# obd25k80.net
KiCad netlist of a schematic drawn in EAGLE
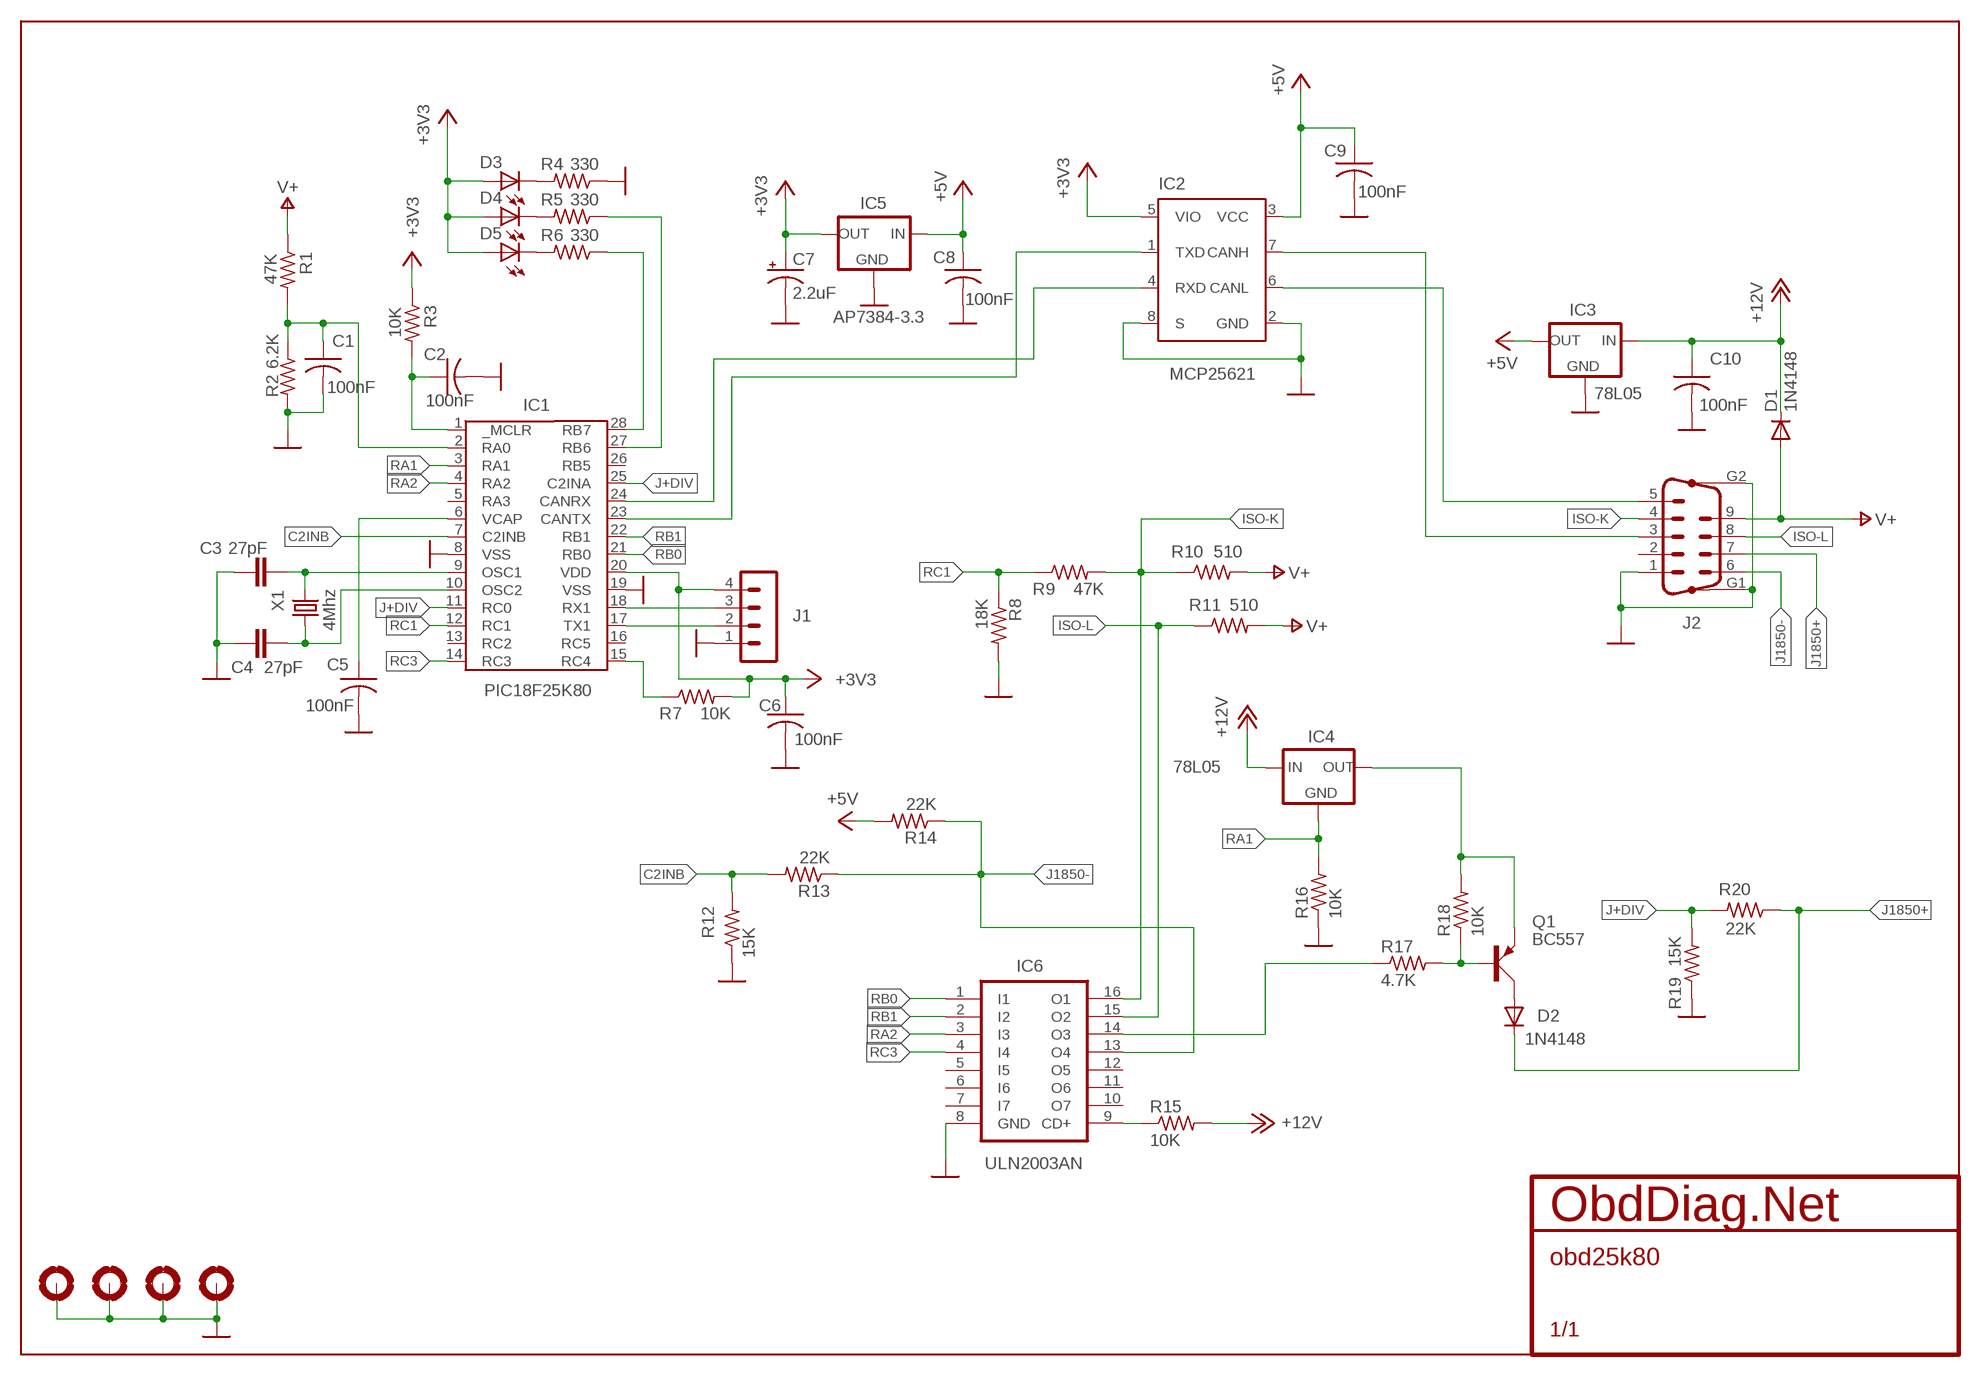
[diagram p0: schematic, sheet 1]

(export (version "E")
  (design (tool "Eeschema 10.0.6"))
  (components
    (comp (ref "C1")
      (value "100nF")
      (footprint "eagle-import:C050-025X075")
      (libsource (lib "eagle-import") (part "C-US050-025X075"))
    )
    (comp (ref "C2")
      (value "100nF")
      (footprint "eagle-import:C050-025X075")
      (libsource (lib "eagle-import") (part "C-US050-025X075"))
    )
    (comp (ref "C3")
      (value "27pF")
      (footprint "eagle-import:C2.5-2")
      (libsource (lib "eagle-import") (part "C2.5/2"))
    )
    (comp (ref "C4")
      (value "27pF")
      (footprint "eagle-import:C2.5-2")
      (libsource (lib "eagle-import") (part "C2.5/2"))
    )
    (comp (ref "C5")
      (value "100nF")
      (footprint "eagle-import:C050-025X075")
      (libsource (lib "eagle-import") (part "C-US050-025X075"))
    )
    (comp (ref "C6")
      (value "100nF")
      (footprint "eagle-import:C050-025X075")
      (libsource (lib "eagle-import") (part "C-US050-025X075"))
    )
    (comp (ref "C7")
      (value "2.2uF")
      (footprint "eagle-import:E2,5-5")
      (libsource (lib "eagle-import") (part "CPOL-USE2.5-5"))
    )
    (comp (ref "C8")
      (value "100nF")
      (footprint "eagle-import:C050-025X075")
      (libsource (lib "eagle-import") (part "C-US050-025X075"))
    )
    (comp (ref "C9")
      (value "100nF")
      (footprint "eagle-import:C050-025X075")
      (libsource (lib "eagle-import") (part "C-US050-025X075"))
    )
    (comp (ref "C10")
      (value "100nF")
      (footprint "eagle-import:C050-025X075")
      (libsource (lib "eagle-import") (part "C-US050-025X075"))
    )
    (comp (ref "D1")
      (value "1N4148")
      (footprint "eagle-import:D035-10M")
      (libsource (lib "eagle-import") (part "1N4148M"))
    )
    (comp (ref "D2")
      (value "1N4148")
      (footprint "eagle-import:D035-10M")
      (libsource (lib "eagle-import") (part "1N4148M"))
    )
    (comp (ref "D3")
      (value "LED5MM")
      (footprint "eagle-import:LED5MM")
      (libsource (lib "eagle-import") (part "LED5MM"))
    )
    (comp (ref "D4")
      (value "LED5MM")
      (footprint "eagle-import:LED5MM")
      (libsource (lib "eagle-import") (part "LED5MM"))
    )
    (comp (ref "D5")
      (value "LED5MM")
      (footprint "eagle-import:LED5MM")
      (libsource (lib "eagle-import") (part "LED5MM"))
    )
    (comp (ref "H1")
      (value "MOUNT-PAD-ROUND2.8")
      (footprint "eagle-import:2,8-PAD")
      (libsource (lib "eagle-import") (part "MOUNT-PAD-ROUND2.8"))
    )
    (comp (ref "H2")
      (value "MOUNT-PAD-ROUND2.8")
      (footprint "eagle-import:2,8-PAD")
      (libsource (lib "eagle-import") (part "MOUNT-PAD-ROUND2.8"))
    )
    (comp (ref "H3")
      (value "MOUNT-PAD-ROUND2.8")
      (footprint "eagle-import:2,8-PAD")
      (libsource (lib "eagle-import") (part "MOUNT-PAD-ROUND2.8"))
    )
    (comp (ref "H4")
      (value "MOUNT-PAD-ROUND2.8")
      (footprint "eagle-import:2,8-PAD")
      (libsource (lib "eagle-import") (part "MOUNT-PAD-ROUND2.8"))
    )
    (comp (ref "IC1")
      (value "PIC18F25K80")
      (footprint "eagle-import:DIL28")
      (libsource (lib "eagle-import") (part "PIC18F25K80-2"))
    )
    (comp (ref "IC2")
      (value "MCP25621")
      (footprint "eagle-import:DIL8")
      (libsource (lib "eagle-import") (part "MCP25621"))
    )
    (comp (ref "IC3")
      (value "78L05")
      (footprint "eagle-import:78LXX")
      (libsource (lib "eagle-import") (part "78LXX"))
    )
    (comp (ref "IC4")
      (value "78L05")
      (footprint "eagle-import:78LXX")
      (libsource (lib "eagle-import") (part "78LXX"))
    )
    (comp (ref "IC5")
      (value "AP7384-3.3")
      (footprint "eagle-import:TO92")
      (libsource (lib "eagle-import") (part "AP7384"))
    )
    (comp (ref "IC6")
      (value "ULN2003AN")
      (footprint "eagle-import:DIL16")
      (libsource (lib "eagle-import") (part "ULN2003AN"))
    )
    (comp (ref "J1")
      (value "MA04-1")
      (footprint "eagle-import:MA04-1")
      (libsource (lib "eagle-import") (part "MA04-1"))
    )
    (comp (ref "J2")
      (value "DB9-M")
      (footprint "eagle-import:M09HP")
      (libsource (lib "eagle-import") (part "M09HP"))
    )
    (comp (ref "Q1")
      (value "BC557")
      (footprint "eagle-import:SOT54A")
      (libsource (lib "eagle-import") (part "BC557"))
    )
    (comp (ref "R1")
      (value "47K")
      (footprint "eagle-import:0207_10")
      (libsource (lib "eagle-import") (part "R-US_0207/10"))
    )
    (comp (ref "R2")
      (value "6.2K")
      (footprint "eagle-import:0207_10")
      (libsource (lib "eagle-import") (part "R-US_0207/10"))
    )
    (comp (ref "R3")
      (value "10K")
      (footprint "eagle-import:0207_10")
      (libsource (lib "eagle-import") (part "R-US_0207/10"))
    )
    (comp (ref "R4")
      (value "330")
      (footprint "eagle-import:0207_10")
      (libsource (lib "eagle-import") (part "R-US_0207/10"))
    )
    (comp (ref "R5")
      (value "330")
      (footprint "eagle-import:0207_10")
      (libsource (lib "eagle-import") (part "R-US_0207/10"))
    )
    (comp (ref "R6")
      (value "330")
      (footprint "eagle-import:0207_10")
      (libsource (lib "eagle-import") (part "R-US_0207/10"))
    )
    (comp (ref "R7")
      (value "10K")
      (footprint "eagle-import:0207_10")
      (libsource (lib "eagle-import") (part "R-US_0207/10"))
    )
    (comp (ref "R8")
      (value "18K")
      (footprint "eagle-import:0207_10")
      (libsource (lib "eagle-import") (part "R-US_0207/10"))
    )
    (comp (ref "R9")
      (value "47K")
      (footprint "eagle-import:0207_10")
      (libsource (lib "eagle-import") (part "R-US_0207/10"))
    )
    (comp (ref "R10")
      (value "510")
      (footprint "eagle-import:0207_10")
      (libsource (lib "eagle-import") (part "R-US_0207/10"))
    )
    (comp (ref "R11")
      (value "510")
      (footprint "eagle-import:0207_10")
      (libsource (lib "eagle-import") (part "R-US_0207/10"))
    )
    (comp (ref "R12")
      (value "15K")
      (footprint "eagle-import:0207_10")
      (libsource (lib "eagle-import") (part "R-US_0207/10"))
    )
    (comp (ref "R13")
      (value "22K")
      (footprint "eagle-import:0207_10")
      (libsource (lib "eagle-import") (part "R-US_0207/10"))
    )
    (comp (ref "R14")
      (value "22K")
      (footprint "eagle-import:0207_10")
      (libsource (lib "eagle-import") (part "R-US_0207/10"))
    )
    (comp (ref "R15")
      (value "10K")
      (footprint "eagle-import:0207_10")
      (libsource (lib "eagle-import") (part "R-US_0207/10"))
    )
    (comp (ref "R16")
      (value "10K")
      (footprint "eagle-import:0207_10")
      (libsource (lib "eagle-import") (part "R-US_0207/10"))
    )
    (comp (ref "R17")
      (value "4.7K")
      (footprint "eagle-import:0207_10")
      (libsource (lib "eagle-import") (part "R-US_0207/10"))
    )
    (comp (ref "R18")
      (value "10K")
      (footprint "eagle-import:0207_10")
      (libsource (lib "eagle-import") (part "R-US_0207/10"))
    )
    (comp (ref "R19")
      (value "15K")
      (footprint "eagle-import:0207_10")
      (libsource (lib "eagle-import") (part "R-US_0207/10"))
    )
    (comp (ref "R20")
      (value "22K")
      (footprint "eagle-import:0207_10")
      (libsource (lib "eagle-import") (part "R-US_0207/10"))
    )
    (comp (ref "X1")
      (value "4Mhz")
      (footprint "eagle-import:HC49_S")
      (libsource (lib "eagle-import") (part "CRYTALHC49S"))
    )
  )
  (nets
    (net (code "1") (name "+3V3") (class "Default")
      (node (ref "C6") (pin "1") (pinfunction "1_1") (pintype "passive"))
      (node (ref "C7") (pin "+") (pinfunction "+_+") (pintype "passive"))
      (node (ref "D3") (pin "A") (pinfunction "A_A") (pintype "passive"))
      (node (ref "D4") (pin "A") (pinfunction "A_A") (pintype "passive"))
      (node (ref "D5") (pin "A") (pinfunction "A_A") (pintype "passive"))
      (node (ref "IC1") (pin "20") (pinfunction "VDD_20") (pintype "power_in"))
      (node (ref "IC2") (pin "5") (pinfunction "VIO_5") (pintype "power_in"))
      (node (ref "IC5") (pin "3") (pinfunction "OUT_3") (pintype "passive"))
      (node (ref "J1") (pin "4") (pinfunction "4_4") (pintype "passive"))
      (node (ref "R3") (pin "1") (pinfunction "1_1") (pintype "passive"))
      (node (ref "R7") (pin "2") (pinfunction "2_2") (pintype "passive"))
    )
    (net (code "2") (name "+5V") (class "Default")
      (node (ref "C8") (pin "1") (pinfunction "1_1") (pintype "passive"))
      (node (ref "C9") (pin "1") (pinfunction "1_1") (pintype "passive"))
      (node (ref "IC2") (pin "3") (pinfunction "VCC_3") (pintype "power_in"))
      (node (ref "IC3") (pin "OUT") (pinfunction "OUT_OUT") (pintype "passive"))
      (node (ref "IC5") (pin "1") (pinfunction "IN_1") (pintype "input"))
      (node (ref "R14") (pin "2") (pinfunction "2_2") (pintype "passive"))
    )
    (net (code "3") (name "+12V") (class "Default")
      (node (ref "C10") (pin "1") (pinfunction "1_1") (pintype "passive"))
      (node (ref "D1") (pin "C") (pinfunction "C_C") (pintype "passive"))
      (node (ref "IC3") (pin "IN") (pinfunction "IN_IN") (pintype "input"))
      (node (ref "IC4") (pin "IN") (pinfunction "IN_IN") (pintype "input"))
      (node (ref "R15") (pin "2") (pinfunction "2_2") (pintype "passive"))
    )
    (net (code "4") (name "C2INB") (class "Default")
      (node (ref "IC1") (pin "7") (pinfunction "C2INB_7") (pintype "input"))
      (node (ref "R12") (pin "2") (pinfunction "2_2") (pintype "passive"))
      (node (ref "R13") (pin "2") (pinfunction "2_2") (pintype "passive"))
    )
    (net (code "5") (name "GND") (class "Default")
      (node (ref "C1") (pin "2") (pinfunction "2_2") (pintype "passive"))
      (node (ref "C10") (pin "2") (pinfunction "2_2") (pintype "passive"))
      (node (ref "C2") (pin "2") (pinfunction "2_2") (pintype "passive"))
      (node (ref "C3") (pin "1") (pinfunction "1_1") (pintype "passive"))
      (node (ref "C4") (pin "2") (pinfunction "2_2") (pintype "passive"))
      (node (ref "C5") (pin "2") (pinfunction "2_2") (pintype "passive"))
      (node (ref "C6") (pin "2") (pinfunction "2_2") (pintype "passive"))
      (node (ref "C7") (pin "-") (pinfunction "-_-") (pintype "passive"))
      (node (ref "C8") (pin "2") (pinfunction "2_2") (pintype "passive"))
      (node (ref "C9") (pin "2") (pinfunction "2_2") (pintype "passive"))
      (node (ref "H1") (pin "B2,8") (pinfunction "MOUNT_B2,8") (pintype "passive"))
      (node (ref "H2") (pin "B2,8") (pinfunction "MOUNT_B2,8") (pintype "passive"))
      (node (ref "H3") (pin "B2,8") (pinfunction "MOUNT_B2,8") (pintype "passive"))
      (node (ref "H4") (pin "B2,8") (pinfunction "MOUNT_B2,8") (pintype "passive"))
      (node (ref "IC1") (pin "19") (pinfunction "VSS_19") (pintype "power_in"))
      (node (ref "IC1") (pin "8") (pinfunction "VSS_8") (pintype "power_in"))
      (node (ref "IC2") (pin "2") (pinfunction "GND_2") (pintype "power_in"))
      (node (ref "IC2") (pin "8") (pinfunction "S_8") (pintype "input"))
      (node (ref "IC3") (pin "GND") (pinfunction "GND_GND") (pintype "input"))
      (node (ref "IC5") (pin "2") (pinfunction "GND_2") (pintype "input"))
      (node (ref "IC6") (pin "8") (pinfunction "GND_8") (pintype "power_in"))
      (node (ref "J1") (pin "1") (pinfunction "1_1") (pintype "passive"))
      (node (ref "J2") (pin "1") (pinfunction "1_1") (pintype "passive"))
      (node (ref "J2") (pin "G1") (pinfunction "G1_G1") (pintype "passive"))
      (node (ref "J2") (pin "G2") (pinfunction "G2_G2") (pintype "passive"))
      (node (ref "R12") (pin "1") (pinfunction "1_1") (pintype "passive"))
      (node (ref "R16") (pin "1") (pinfunction "1_1") (pintype "passive"))
      (node (ref "R19") (pin "1") (pinfunction "1_1") (pintype "passive"))
      (node (ref "R2") (pin "2") (pinfunction "2_2") (pintype "passive"))
      (node (ref "R4") (pin "1") (pinfunction "1_1") (pintype "passive"))
      (node (ref "R8") (pin "2") (pinfunction "2_2") (pintype "passive"))
    )
    (net (code "6") (name "ISO-K") (class "Default")
      (node (ref "IC6") (pin "16") (pinfunction "O1_16") (pintype "open_collector"))
      (node (ref "J2") (pin "4") (pinfunction "4_4") (pintype "passive"))
      (node (ref "R10") (pin "1") (pinfunction "1_1") (pintype "passive"))
      (node (ref "R9") (pin "2") (pinfunction "2_2") (pintype "passive"))
    )
    (net (code "7") (name "ISO-L") (class "Default")
      (node (ref "IC6") (pin "15") (pinfunction "O2_15") (pintype "open_collector"))
      (node (ref "J2") (pin "8") (pinfunction "8_8") (pintype "passive"))
      (node (ref "R11") (pin "1") (pinfunction "1_1") (pintype "passive"))
    )
    (net (code "8") (name "J+DIV") (class "Default")
      (node (ref "IC1") (pin "11") (pinfunction "RC0_11") (pintype "bidirectional"))
      (node (ref "IC1") (pin "25") (pinfunction "C2INA_25") (pintype "input"))
      (node (ref "R19") (pin "2") (pinfunction "2_2") (pintype "passive"))
      (node (ref "R20") (pin "2") (pinfunction "2_2") (pintype "passive"))
    )
    (net (code "9") (name "J1850+") (class "Default")
      (node (ref "D2") (pin "C") (pinfunction "C_C") (pintype "passive"))
      (node (ref "J2") (pin "7") (pinfunction "7_7") (pintype "passive"))
      (node (ref "R20") (pin "1") (pinfunction "1_1") (pintype "passive"))
    )
    (net (code "10") (name "J1850-") (class "Default")
      (node (ref "IC6") (pin "13") (pinfunction "O4_13") (pintype "open_collector"))
      (node (ref "J2") (pin "6") (pinfunction "6_6") (pintype "passive"))
      (node (ref "R13") (pin "1") (pinfunction "1_1") (pintype "passive"))
      (node (ref "R14") (pin "1") (pinfunction "1_1") (pintype "passive"))
    )
    (net (code "11") (name "Net-(D2-PadA)") (class "Default")
      (node (ref "D2") (pin "A") (pinfunction "A_A") (pintype "passive"))
      (node (ref "Q1") (pin "C") (pinfunction "C_C") (pintype "passive"))
    )
    (net (code "12") (name "Net-(D3-C)") (class "Default")
      (node (ref "D3") (pin "K") (pinfunction "C_K") (pintype "passive"))
      (node (ref "R4") (pin "2") (pinfunction "2_2") (pintype "passive"))
    )
    (net (code "13") (name "Net-(D4-C)") (class "Default")
      (node (ref "D4") (pin "K") (pinfunction "C_K") (pintype "passive"))
      (node (ref "R5") (pin "2") (pinfunction "2_2") (pintype "passive"))
    )
    (net (code "14") (name "Net-(D5-C)") (class "Default")
      (node (ref "D5") (pin "K") (pinfunction "C_K") (pintype "passive"))
      (node (ref "R6") (pin "2") (pinfunction "2_2") (pintype "passive"))
    )
    (net (code "15") (name "Net-(IC1-CANRX)") (class "Default")
      (node (ref "IC1") (pin "24") (pinfunction "CANRX_24") (pintype "bidirectional"))
      (node (ref "IC2") (pin "4") (pinfunction "RXD_4") (pintype "output"))
    )
    (net (code "16") (name "Net-(IC1-CANTX)") (class "Default")
      (node (ref "IC1") (pin "23") (pinfunction "CANTX_23") (pintype "bidirectional"))
      (node (ref "IC2") (pin "1") (pinfunction "TXD_1") (pintype "input"))
    )
    (net (code "17") (name "Net-(IC1-OSC1)") (class "Default")
      (node (ref "C3") (pin "2") (pinfunction "2_2") (pintype "passive"))
      (node (ref "IC1") (pin "9") (pinfunction "OSC1_9") (pintype "bidirectional"))
      (node (ref "X1") (pin "2") (pinfunction "2_2") (pintype "passive"))
    )
    (net (code "18") (name "Net-(IC1-OSC2)") (class "Default")
      (node (ref "C4") (pin "1") (pinfunction "1_1") (pintype "passive"))
      (node (ref "IC1") (pin "10") (pinfunction "OSC2_10") (pintype "bidirectional"))
      (node (ref "X1") (pin "1") (pinfunction "1_1") (pintype "passive"))
    )
    (net (code "19") (name "Net-(IC1-RA0)") (class "Default")
      (node (ref "C1") (pin "1") (pinfunction "1_1") (pintype "passive"))
      (node (ref "IC1") (pin "2") (pinfunction "RA0_2") (pintype "bidirectional"))
      (node (ref "R1") (pin "2") (pinfunction "2_2") (pintype "passive"))
      (node (ref "R2") (pin "1") (pinfunction "1_1") (pintype "passive"))
    )
    (net (code "20") (name "Net-(IC1-RB6)") (class "Default")
      (node (ref "IC1") (pin "27") (pinfunction "RB6_27") (pintype "bidirectional"))
      (node (ref "R5") (pin "1") (pinfunction "1_1") (pintype "passive"))
    )
    (net (code "21") (name "Net-(IC1-RB7)") (class "Default")
      (node (ref "IC1") (pin "28") (pinfunction "RB7_28") (pintype "bidirectional"))
      (node (ref "R6") (pin "1") (pinfunction "1_1") (pintype "passive"))
    )
    (net (code "22") (name "Net-(IC1-RC4)") (class "Default")
      (node (ref "IC1") (pin "15") (pinfunction "RC4_15") (pintype "bidirectional"))
      (node (ref "R7") (pin "1") (pinfunction "1_1") (pintype "passive"))
    )
    (net (code "23") (name "Net-(IC1-RX1)") (class "Default")
      (node (ref "IC1") (pin "18") (pinfunction "RX1_18") (pintype "bidirectional"))
      (node (ref "J1") (pin "3") (pinfunction "3_3") (pintype "passive"))
    )
    (net (code "24") (name "Net-(IC1-TX1)") (class "Default")
      (node (ref "IC1") (pin "17") (pinfunction "TX1_17") (pintype "bidirectional"))
      (node (ref "J1") (pin "2") (pinfunction "2_2") (pintype "passive"))
    )
    (net (code "25") (name "Net-(IC1-VCAP)") (class "Default")
      (node (ref "C5") (pin "1") (pinfunction "1_1") (pintype "passive"))
      (node (ref "IC1") (pin "6") (pinfunction "VCAP_6") (pintype "passive"))
    )
    (net (code "26") (name "Net-(IC1-_MCLR)") (class "Default")
      (node (ref "C2") (pin "1") (pinfunction "1_1") (pintype "passive"))
      (node (ref "IC1") (pin "1") (pinfunction "_MCLR_1") (pintype "bidirectional"))
      (node (ref "R3") (pin "2") (pinfunction "2_2") (pintype "passive"))
    )
    (net (code "27") (name "Net-(IC2-CANH)") (class "Default")
      (node (ref "IC2") (pin "7") (pinfunction "CANH_7") (pintype "bidirectional"))
      (node (ref "J2") (pin "3") (pinfunction "3_3") (pintype "passive"))
    )
    (net (code "28") (name "Net-(IC2-CANL)") (class "Default")
      (node (ref "IC2") (pin "6") (pinfunction "CANL_6") (pintype "bidirectional"))
      (node (ref "J2") (pin "5") (pinfunction "5_5") (pintype "passive"))
    )
    (net (code "29") (name "Net-(IC4-PadOUT)") (class "Default")
      (node (ref "IC4") (pin "OUT") (pinfunction "OUT_OUT") (pintype "passive"))
      (node (ref "Q1") (pin "E") (pinfunction "E_E") (pintype "passive"))
      (node (ref "R18") (pin "2") (pinfunction "2_2") (pintype "passive"))
    )
    (net (code "30") (name "Net-(IC6-CD+)") (class "Default")
      (node (ref "IC6") (pin "9") (pinfunction "CD+_9") (pintype "passive"))
      (node (ref "R15") (pin "1") (pinfunction "1_1") (pintype "passive"))
    )
    (net (code "31") (name "Net-(IC6-O3)") (class "Default")
      (node (ref "IC6") (pin "14") (pinfunction "O3_14") (pintype "open_collector"))
      (node (ref "R17") (pin "1") (pinfunction "1_1") (pintype "passive"))
    )
    (net (code "32") (name "Net-(Q1-PadB)") (class "Default")
      (node (ref "Q1") (pin "B") (pinfunction "B_B") (pintype "passive"))
      (node (ref "R17") (pin "2") (pinfunction "2_2") (pintype "passive"))
      (node (ref "R18") (pin "1") (pinfunction "1_1") (pintype "passive"))
    )
    (net (code "33") (name "RA1") (class "Default")
      (node (ref "IC1") (pin "3") (pinfunction "RA1_3") (pintype "bidirectional"))
      (node (ref "IC4") (pin "GND") (pinfunction "GND_GND") (pintype "input"))
      (node (ref "R16") (pin "2") (pinfunction "2_2") (pintype "passive"))
    )
    (net (code "34") (name "RA2") (class "Default")
      (node (ref "IC1") (pin "4") (pinfunction "RA2_4") (pintype "bidirectional"))
      (node (ref "IC6") (pin "3") (pinfunction "I3_3") (pintype "input"))
    )
    (net (code "35") (name "RB0") (class "Default")
      (node (ref "IC1") (pin "21") (pinfunction "RB0_21") (pintype "bidirectional"))
      (node (ref "IC6") (pin "1") (pinfunction "I1_1") (pintype "input"))
    )
    (net (code "36") (name "RB1") (class "Default")
      (node (ref "IC1") (pin "22") (pinfunction "RB1_22") (pintype "bidirectional"))
      (node (ref "IC6") (pin "2") (pinfunction "I2_2") (pintype "input"))
    )
    (net (code "37") (name "RC1") (class "Default")
      (node (ref "IC1") (pin "12") (pinfunction "RC1_12") (pintype "bidirectional"))
      (node (ref "R8") (pin "1") (pinfunction "1_1") (pintype "passive"))
      (node (ref "R9") (pin "1") (pinfunction "1_1") (pintype "passive"))
    )
    (net (code "38") (name "RC3") (class "Default")
      (node (ref "IC1") (pin "14") (pinfunction "RC3_14") (pintype "bidirectional"))
      (node (ref "IC6") (pin "4") (pinfunction "I4_4") (pintype "input"))
    )
    (net (code "39") (name "V+") (class "Default")
      (node (ref "D1") (pin "A") (pinfunction "A_A") (pintype "passive"))
      (node (ref "J2") (pin "9") (pinfunction "9_9") (pintype "passive"))
      (node (ref "R1") (pin "1") (pinfunction "1_1") (pintype "passive"))
      (node (ref "R10") (pin "2") (pinfunction "2_2") (pintype "passive"))
      (node (ref "R11") (pin "2") (pinfunction "2_2") (pintype "passive"))
    )
    (net (code "40") (name "unconnected-(IC1-RA3-Pad5)") (class "Default")
      (node (ref "IC1") (pin "5") (pinfunction "RA3_5") (pintype "bidirectional"))
    )
    (net (code "41") (name "unconnected-(IC1-RB5-Pad26)") (class "Default")
      (node (ref "IC1") (pin "26") (pinfunction "RB5_26") (pintype "bidirectional"))
    )
    (net (code "42") (name "unconnected-(IC1-RC2-Pad13)") (class "Default")
      (node (ref "IC1") (pin "13") (pinfunction "RC2_13") (pintype "bidirectional"))
    )
    (net (code "43") (name "unconnected-(IC1-RC5-Pad16)") (class "Default")
      (node (ref "IC1") (pin "16") (pinfunction "RC5_16") (pintype "bidirectional"))
    )
    (net (code "44") (name "unconnected-(IC6-I5-Pad5)") (class "Default")
      (node (ref "IC6") (pin "5") (pinfunction "I5_5") (pintype "input"))
    )
    (net (code "45") (name "unconnected-(IC6-I6-Pad6)") (class "Default")
      (node (ref "IC6") (pin "6") (pinfunction "I6_6") (pintype "input"))
    )
    (net (code "46") (name "unconnected-(IC6-I7-Pad7)") (class "Default")
      (node (ref "IC6") (pin "7") (pinfunction "I7_7") (pintype "input"))
    )
    (net (code "47") (name "unconnected-(IC6-O5-Pad12)") (class "Default")
      (node (ref "IC6") (pin "12") (pinfunction "O5_12") (pintype "open_collector"))
    )
    (net (code "48") (name "unconnected-(IC6-O6-Pad11)") (class "Default")
      (node (ref "IC6") (pin "11") (pinfunction "O6_11") (pintype "open_collector"))
    )
    (net (code "49") (name "unconnected-(IC6-O7-Pad10)") (class "Default")
      (node (ref "IC6") (pin "10") (pinfunction "O7_10") (pintype "open_collector"))
    )
    (net (code "50") (name "unconnected-(J2-Pad2)") (class "Default")
      (node (ref "J2") (pin "2") (pinfunction "2_2") (pintype "passive"))
    )
  )
)
